# FPGA_Peripherals_Control.net
KiCad netlist of a schematic drawn in Altium Designer
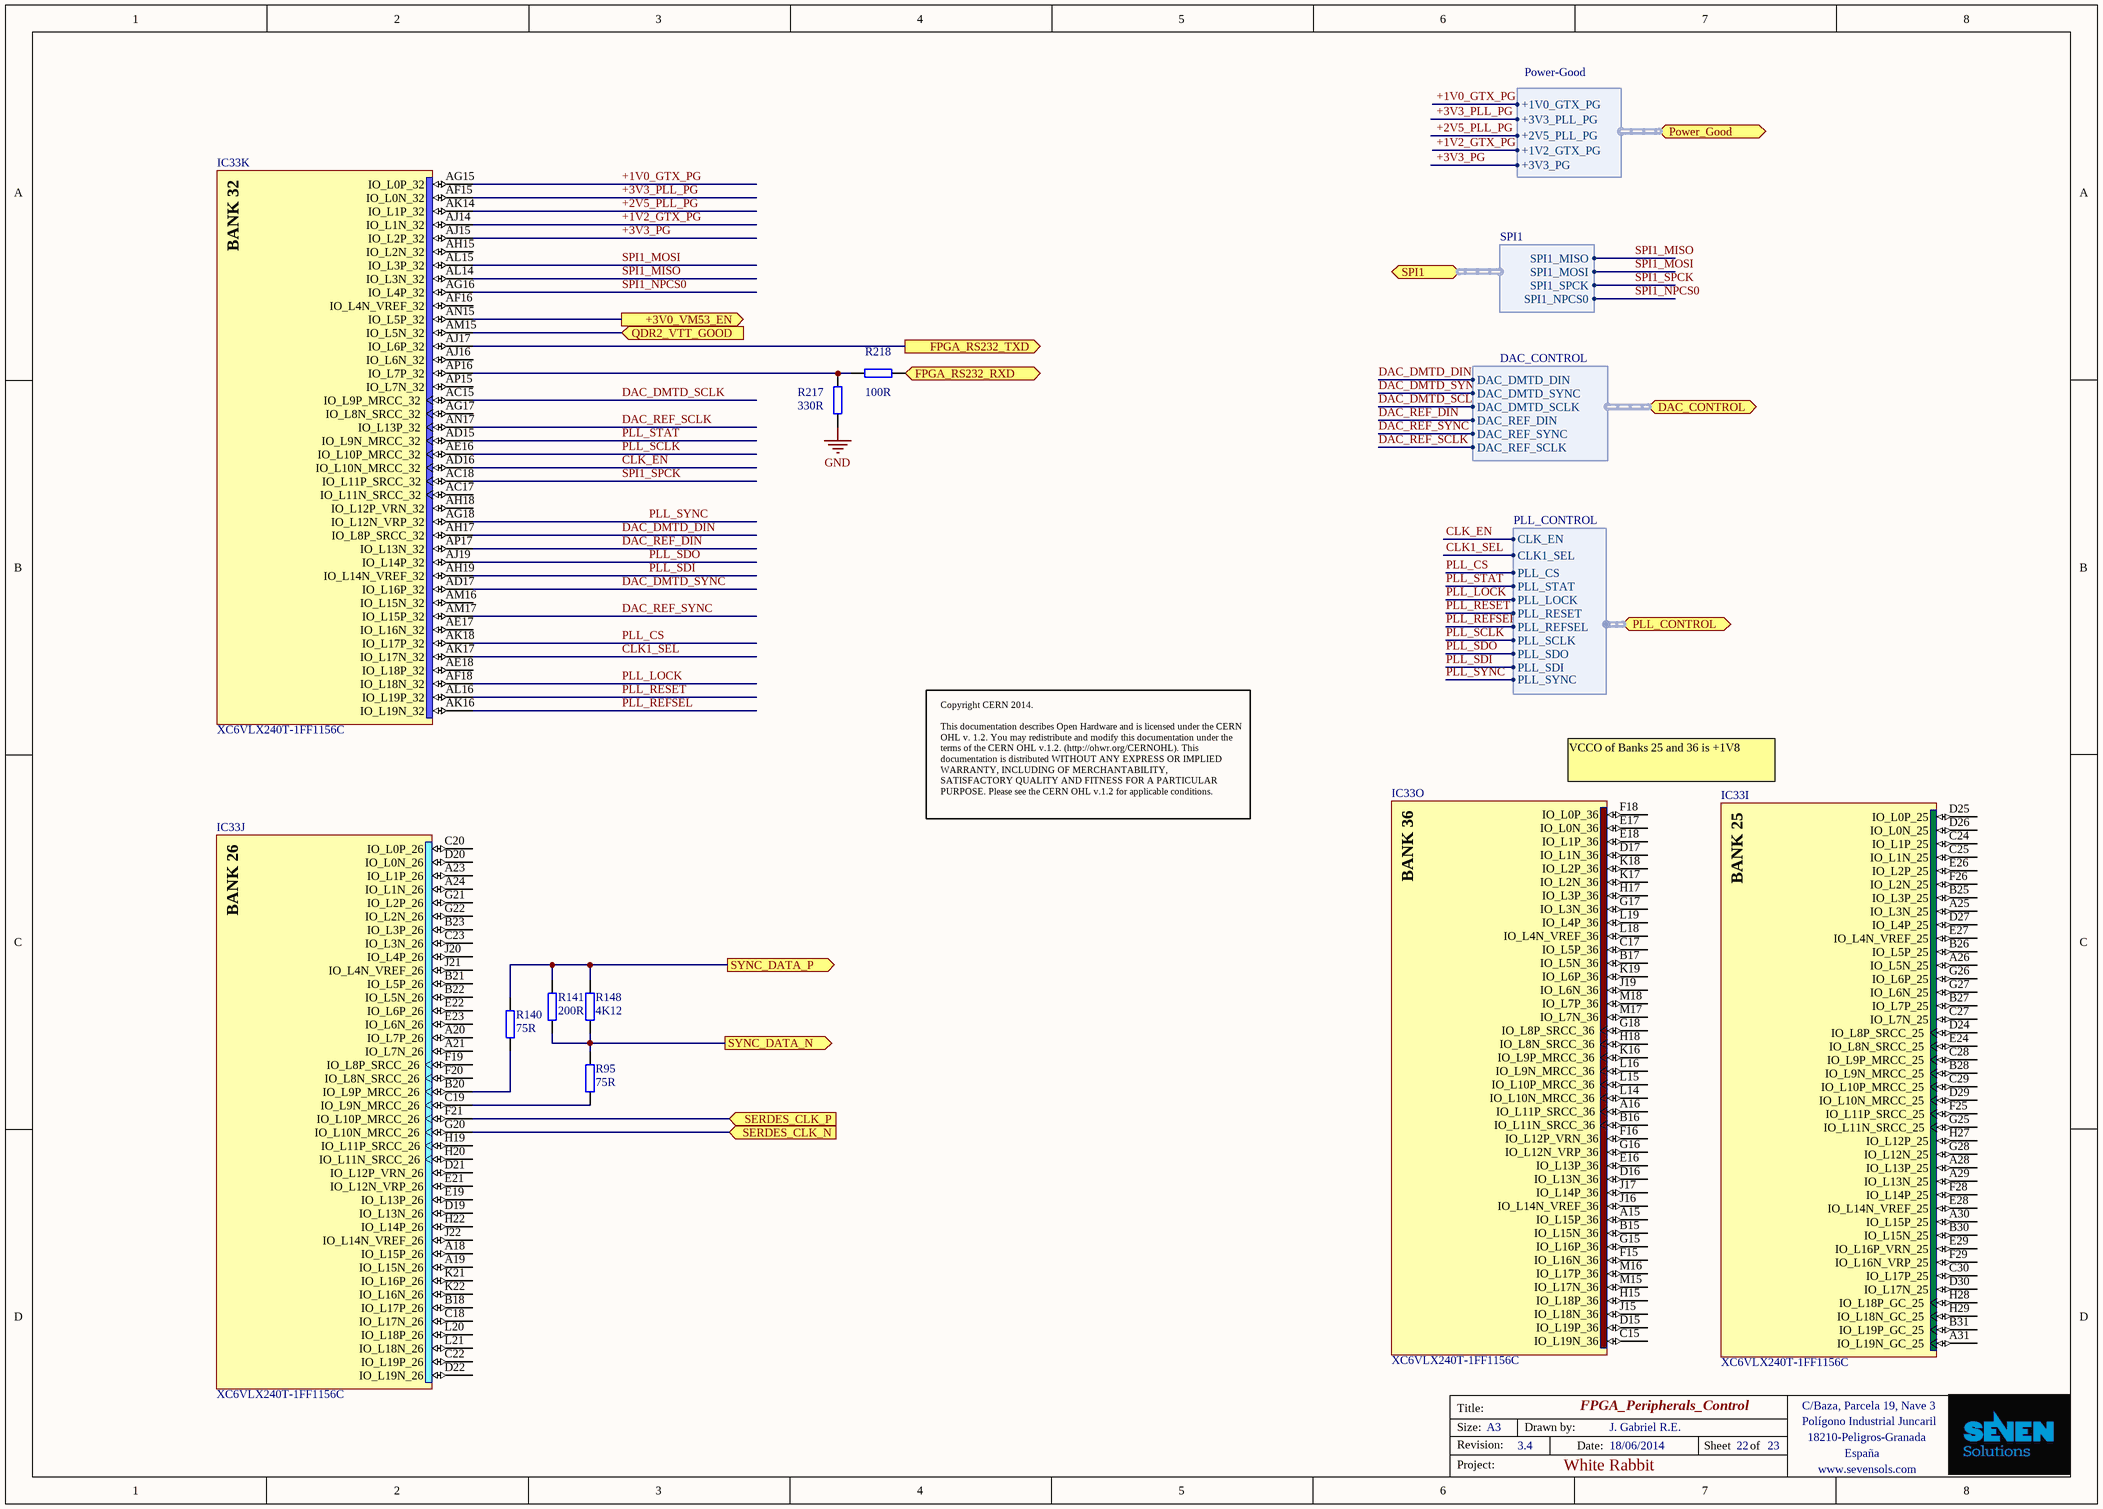
[diagram p0: FPGA_Peripherals_Control.SchDoc]

(export (version "E")
  (design (tool "Eeschema 10.0.6"))
  (components
    (comp (ref "IC33")
      (value "XC6VLX240T-1FF1156C")
      (footprint "FF1156")
      (fields (field (name "PUBLISHER") "Altium Limited"))
      (libsource (lib "Xilinx Virtex-6") (part "XC6VLX240T-1FF1156C"))
    )
    (comp (ref "R95")
      (value "75R")
      (footprint "0402")
      (description "SMD Resistor")
      (fields (field (name "TOLERANCE") "±1%"))
      (libsource (lib "wr_switch") (part "RES_SMD"))
    )
    (comp (ref "R140")
      (value "75R")
      (footprint "0402")
      (description "SMD Resistor")
      (fields (field (name "TOLERANCE") "±1%"))
      (libsource (lib "wr_switch") (part "RES_SMD"))
    )
    (comp (ref "R141")
      (value "200R")
      (footprint "0402")
      (description "SMD Resistor")
      (fields (field (name "TOLERANCE") "±1%"))
      (libsource (lib "wr_switch") (part "RES_SMD"))
    )
    (comp (ref "R148")
      (value "4K12")
      (footprint "0402")
      (description "SMD Resistor")
      (fields (field (name "TOLERANCE") "±1%"))
      (libsource (lib "wr_switch") (part "RES_SMD"))
    )
    (comp (ref "R217")
      (value "330R")
      (footprint "0402")
      (description "SMD Resistor")
      (fields (field (name "TOLERANCE") "±1%"))
      (libsource (lib "wr_switch") (part "RES_SMD"))
    )
    (comp (ref "R218")
      (value "100R")
      (footprint "0402")
      (description "SMD Resistor")
      (fields (field (name "TOLERANCE") "±1%"))
      (libsource (lib "wr_switch") (part "RES_SMD"))
    )
  )
  (nets
    (net (code "5") (name "/+1V0_GTX_PG") (class "Default")
      (node (ref "IC33") (pin "AG15") (pinfunction "IO_L0P_32_AG15") (pintype "bidirectional"))
    )
    (net (code "6") (name "/+1V2_GTX_PG") (class "Default")
      (node (ref "IC33") (pin "AJ14") (pinfunction "IO_L1N_32_AJ14") (pintype "bidirectional"))
    )
    (net (code "7") (name "/+2V5_PLL_PG") (class "Default")
      (node (ref "IC33") (pin "AK14") (pinfunction "IO_L1P_32_AK14") (pintype "bidirectional"))
    )
    (net (code "8") (name "/+3V0_VM53_EN") (class "Default")
      (node (ref "IC33") (pin "AN15") (pinfunction "IO_L5P_32_AN15") (pintype "bidirectional"))
    )
    (net (code "9") (name "/+3V3_PG") (class "Default")
      (node (ref "IC33") (pin "AJ15") (pinfunction "IO_L2P_32_AJ15") (pintype "bidirectional"))
    )
    (net (code "10") (name "/+3V3_PLL_PG") (class "Default")
      (node (ref "IC33") (pin "AF15") (pinfunction "IO_L0N_32_AF15") (pintype "bidirectional"))
    )
    (net (code "11") (name "/CLK1_SEL") (class "Default")
      (node (ref "IC33") (pin "AK17") (pinfunction "IO_L17N_32_AK17") (pintype "bidirectional"))
    )
    (net (code "12") (name "/CLK_EN") (class "Default")
      (node (ref "IC33") (pin "AD16") (pinfunction "IO_L10N_MRCC_32_AD16") (pintype "bidirectional"))
    )
    (net (code "13") (name "/DAC_DMTD_DIN") (class "Default")
      (node (ref "IC33") (pin "AH17") (pinfunction "IO_L8P_SRCC_32_AH17") (pintype "bidirectional"))
    )
    (net (code "14") (name "/DAC_DMTD_SCLK") (class "Default")
      (node (ref "IC33") (pin "AC15") (pinfunction "IO_L9P_MRCC_32_AC15") (pintype "bidirectional"))
    )
    (net (code "15") (name "/DAC_DMTD_SYNC") (class "Default")
      (node (ref "IC33") (pin "AD17") (pinfunction "IO_L16P_32_AD17") (pintype "bidirectional"))
    )
    (net (code "16") (name "/DAC_REF_DIN") (class "Default")
      (node (ref "IC33") (pin "AP17") (pinfunction "IO_L13N_32_AP17") (pintype "bidirectional"))
    )
    (net (code "17") (name "/DAC_REF_SCLK") (class "Default")
      (node (ref "IC33") (pin "AN17") (pinfunction "IO_L13P_32_AN17") (pintype "bidirectional"))
    )
    (net (code "18") (name "/DAC_REF_SYNC") (class "Default")
      (node (ref "IC33") (pin "AM17") (pinfunction "IO_L15P_32_AM17") (pintype "bidirectional"))
    )
    (net (code "19") (name "/FPGA_RS232_RXD") (class "Default")
      (node (ref "R218") (pin "1") (pinfunction "1_1") (pintype "passive"))
    )
    (net (code "20") (name "/FPGA_RS232_TXD") (class "Default")
      (node (ref "IC33") (pin "AJ17") (pinfunction "IO_L6P_32_AJ17") (pintype "bidirectional"))
    )
    (net (code "21") (name "/PLL_CS") (class "Default")
      (node (ref "IC33") (pin "AK18") (pinfunction "IO_L17P_32_AK18") (pintype "bidirectional"))
    )
    (net (code "22") (name "/PLL_LOCK") (class "Default")
      (node (ref "IC33") (pin "AF18") (pinfunction "IO_L18N_32_AF18") (pintype "bidirectional"))
    )
    (net (code "23") (name "/PLL_REFSEL") (class "Default")
      (node (ref "IC33") (pin "AK16") (pinfunction "IO_L19N_32_AK16") (pintype "bidirectional"))
    )
    (net (code "24") (name "/PLL_RESET") (class "Default")
      (node (ref "IC33") (pin "AL16") (pinfunction "IO_L19P_32_AL16") (pintype "bidirectional"))
    )
    (net (code "25") (name "/PLL_SCLK") (class "Default")
      (node (ref "IC33") (pin "AE16") (pinfunction "IO_L10P_MRCC_32_AE16") (pintype "bidirectional"))
    )
    (net (code "26") (name "/PLL_SDI") (class "Default")
      (node (ref "IC33") (pin "AH19") (pinfunction "IO_L14N_VREF_32_AH19") (pintype "bidirectional"))
    )
    (net (code "27") (name "/PLL_SDO") (class "Default")
      (node (ref "IC33") (pin "AJ19") (pinfunction "IO_L14P_32_AJ19") (pintype "bidirectional"))
    )
    (net (code "28") (name "/PLL_STAT") (class "Default")
      (node (ref "IC33") (pin "AD15") (pinfunction "IO_L9N_MRCC_32_AD15") (pintype "bidirectional"))
    )
    (net (code "29") (name "/PLL_SYNC") (class "Default")
      (node (ref "IC33") (pin "AG18") (pinfunction "IO_L12N_VRP_32_AG18") (pintype "bidirectional"))
    )
    (net (code "30") (name "/QDR2_VTT_GOOD") (class "Default")
      (node (ref "IC33") (pin "AM15") (pinfunction "IO_L5N_32_AM15") (pintype "bidirectional"))
    )
    (net (code "31") (name "/SERDES_CLK_N") (class "Default")
      (node (ref "IC33") (pin "G20") (pinfunction "IO_L10N_MRCC_26_G20") (pintype "bidirectional"))
    )
    (net (code "32") (name "/SERDES_CLK_P") (class "Default")
      (node (ref "IC33") (pin "F21") (pinfunction "IO_L10P_MRCC_26_F21") (pintype "bidirectional"))
    )
    (net (code "33") (name "/SPI1_MISO") (class "Default")
      (node (ref "IC33") (pin "AL14") (pinfunction "IO_L3N_32_AL14") (pintype "bidirectional"))
    )
    (net (code "34") (name "/SPI1_MOSI") (class "Default")
      (node (ref "IC33") (pin "AL15") (pinfunction "IO_L3P_32_AL15") (pintype "bidirectional"))
    )
    (net (code "35") (name "/SPI1_NPCS0") (class "Default")
      (node (ref "IC33") (pin "AG16") (pinfunction "IO_L4P_32_AG16") (pintype "bidirectional"))
    )
    (net (code "36") (name "/SPI1_SPCK") (class "Default")
      (node (ref "IC33") (pin "AC18") (pinfunction "IO_L11P_SRCC_32_AC18") (pintype "bidirectional"))
    )
    (net (code "37") (name "/SYNC_DATA_N") (class "Default")
      (node (ref "R141") (pin "2") (pinfunction "2_2") (pintype "passive"))
      (node (ref "R148") (pin "1") (pinfunction "1_1") (pintype "passive"))
      (node (ref "R95") (pin "2") (pinfunction "2_2") (pintype "passive"))
    )
    (net (code "38") (name "/SYNC_DATA_P") (class "Default")
      (node (ref "R140") (pin "2") (pinfunction "2_2") (pintype "passive"))
      (node (ref "R141") (pin "1") (pinfunction "1_1") (pintype "passive"))
      (node (ref "R148") (pin "2") (pinfunction "2_2") (pintype "passive"))
    )
    (net (code "43") (name "GND") (class "Default")
      (node (ref "R217") (pin "1") (pinfunction "1_1") (pintype "passive"))
    )
    (net (code "44") (name "Net-(IC33J-IO_L9N_MRCC_26)") (class "Default")
      (node (ref "IC33") (pin "C19") (pinfunction "IO_L9N_MRCC_26_C19") (pintype "bidirectional"))
      (node (ref "R95") (pin "1") (pinfunction "1_1") (pintype "passive"))
    )
    (net (code "45") (name "Net-(IC33J-IO_L9P_MRCC_26)") (class "Default")
      (node (ref "IC33") (pin "B20") (pinfunction "IO_L9P_MRCC_26_B20") (pintype "bidirectional"))
      (node (ref "R140") (pin "1") (pinfunction "1_1") (pintype "passive"))
    )
    (net (code "46") (name "Net-(IC33K-IO_L7P_32)") (class "Default")
      (node (ref "IC33") (pin "AP16") (pinfunction "IO_L7P_32_AP16") (pintype "bidirectional"))
      (node (ref "R217") (pin "2") (pinfunction "2_2") (pintype "passive"))
      (node (ref "R218") (pin "2") (pinfunction "2_2") (pintype "passive"))
    )
    (net (code "47") (name "unconnected-(IC33I-IO_L0N_25-PadD26)") (class "Default")
      (node (ref "IC33") (pin "D26") (pinfunction "IO_L0N_25_D26") (pintype "bidirectional"))
    )
    (net (code "48") (name "unconnected-(IC33I-IO_L0P_25-PadD25)") (class "Default")
      (node (ref "IC33") (pin "D25") (pinfunction "IO_L0P_25_D25") (pintype "bidirectional"))
    )
    (net (code "49") (name "unconnected-(IC33I-IO_L1N_25-PadC25)") (class "Default")
      (node (ref "IC33") (pin "C25") (pinfunction "IO_L1N_25_C25") (pintype "bidirectional"))
    )
    (net (code "50") (name "unconnected-(IC33I-IO_L1P_25-PadC24)") (class "Default")
      (node (ref "IC33") (pin "C24") (pinfunction "IO_L1P_25_C24") (pintype "bidirectional"))
    )
    (net (code "51") (name "unconnected-(IC33I-IO_L2N_25-PadF26)") (class "Default")
      (node (ref "IC33") (pin "F26") (pinfunction "IO_L2N_25_F26") (pintype "bidirectional"))
    )
    (net (code "52") (name "unconnected-(IC33I-IO_L2P_25-PadE26)") (class "Default")
      (node (ref "IC33") (pin "E26") (pinfunction "IO_L2P_25_E26") (pintype "bidirectional"))
    )
    (net (code "53") (name "unconnected-(IC33I-IO_L3N_25-PadA25)") (class "Default")
      (node (ref "IC33") (pin "A25") (pinfunction "IO_L3N_25_A25") (pintype "bidirectional"))
    )
    (net (code "54") (name "unconnected-(IC33I-IO_L3P_25-PadB25)") (class "Default")
      (node (ref "IC33") (pin "B25") (pinfunction "IO_L3P_25_B25") (pintype "bidirectional"))
    )
    (net (code "55") (name "unconnected-(IC33I-IO_L4N_VREF_25-PadE27)") (class "Default")
      (node (ref "IC33") (pin "E27") (pinfunction "IO_L4N_VREF_25_E27") (pintype "bidirectional"))
    )
    (net (code "56") (name "unconnected-(IC33I-IO_L4P_25-PadD27)") (class "Default")
      (node (ref "IC33") (pin "D27") (pinfunction "IO_L4P_25_D27") (pintype "bidirectional"))
    )
    (net (code "57") (name "unconnected-(IC33I-IO_L5N_25-PadA26)") (class "Default")
      (node (ref "IC33") (pin "A26") (pinfunction "IO_L5N_25_A26") (pintype "bidirectional"))
    )
    (net (code "58") (name "unconnected-(IC33I-IO_L5P_25-PadB26)") (class "Default")
      (node (ref "IC33") (pin "B26") (pinfunction "IO_L5P_25_B26") (pintype "bidirectional"))
    )
    (net (code "59") (name "unconnected-(IC33I-IO_L6N_25-PadG27)") (class "Default")
      (node (ref "IC33") (pin "G27") (pinfunction "IO_L6N_25_G27") (pintype "bidirectional"))
    )
    (net (code "60") (name "unconnected-(IC33I-IO_L6P_25-PadG26)") (class "Default")
      (node (ref "IC33") (pin "G26") (pinfunction "IO_L6P_25_G26") (pintype "bidirectional"))
    )
    (net (code "61") (name "unconnected-(IC33I-IO_L7N_25-PadC27)") (class "Default")
      (node (ref "IC33") (pin "C27") (pinfunction "IO_L7N_25_C27") (pintype "bidirectional"))
    )
    (net (code "62") (name "unconnected-(IC33I-IO_L7P_25-PadB27)") (class "Default")
      (node (ref "IC33") (pin "B27") (pinfunction "IO_L7P_25_B27") (pintype "bidirectional"))
    )
    (net (code "63") (name "unconnected-(IC33I-IO_L8N_SRCC_25-PadE24)") (class "Default")
      (node (ref "IC33") (pin "E24") (pinfunction "IO_L8N_SRCC_25_E24") (pintype "bidirectional"))
    )
    (net (code "64") (name "unconnected-(IC33I-IO_L8P_SRCC_25-PadD24)") (class "Default")
      (node (ref "IC33") (pin "D24") (pinfunction "IO_L8P_SRCC_25_D24") (pintype "bidirectional"))
    )
    (net (code "65") (name "unconnected-(IC33I-IO_L9N_MRCC_25-PadB28)") (class "Default")
      (node (ref "IC33") (pin "B28") (pinfunction "IO_L9N_MRCC_25_B28") (pintype "bidirectional"))
    )
    (net (code "66") (name "unconnected-(IC33I-IO_L9P_MRCC_25-PadC28)") (class "Default")
      (node (ref "IC33") (pin "C28") (pinfunction "IO_L9P_MRCC_25_C28") (pintype "bidirectional"))
    )
    (net (code "67") (name "unconnected-(IC33I-IO_L10N_MRCC_25-PadD29)") (class "Default")
      (node (ref "IC33") (pin "D29") (pinfunction "IO_L10N_MRCC_25_D29") (pintype "bidirectional"))
    )
    (net (code "68") (name "unconnected-(IC33I-IO_L10P_MRCC_25-PadC29)") (class "Default")
      (node (ref "IC33") (pin "C29") (pinfunction "IO_L10P_MRCC_25_C29") (pintype "bidirectional"))
    )
    (net (code "69") (name "unconnected-(IC33I-IO_L11N_SRCC_25-PadG25)") (class "Default")
      (node (ref "IC33") (pin "G25") (pinfunction "IO_L11N_SRCC_25_G25") (pintype "bidirectional"))
    )
    (net (code "70") (name "unconnected-(IC33I-IO_L11P_SRCC_25-PadF25)") (class "Default")
      (node (ref "IC33") (pin "F25") (pinfunction "IO_L11P_SRCC_25_F25") (pintype "bidirectional"))
    )
    (net (code "71") (name "unconnected-(IC33I-IO_L12N_25-PadG28)") (class "Default")
      (node (ref "IC33") (pin "G28") (pinfunction "IO_L12N_25_G28") (pintype "bidirectional"))
    )
    (net (code "72") (name "unconnected-(IC33I-IO_L12P_25-PadH27)") (class "Default")
      (node (ref "IC33") (pin "H27") (pinfunction "IO_L12P_25_H27") (pintype "bidirectional"))
    )
    (net (code "73") (name "unconnected-(IC33I-IO_L13N_25-PadA29)") (class "Default")
      (node (ref "IC33") (pin "A29") (pinfunction "IO_L13N_25_A29") (pintype "bidirectional"))
    )
    (net (code "74") (name "unconnected-(IC33I-IO_L13P_25-PadA28)") (class "Default")
      (node (ref "IC33") (pin "A28") (pinfunction "IO_L13P_25_A28") (pintype "bidirectional"))
    )
    (net (code "75") (name "unconnected-(IC33I-IO_L14N_VREF_25-PadE28)") (class "Default")
      (node (ref "IC33") (pin "E28") (pinfunction "IO_L14N_VREF_25_E28") (pintype "bidirectional"))
    )
    (net (code "76") (name "unconnected-(IC33I-IO_L14P_25-PadF28)") (class "Default")
      (node (ref "IC33") (pin "F28") (pinfunction "IO_L14P_25_F28") (pintype "bidirectional"))
    )
    (net (code "77") (name "unconnected-(IC33I-IO_L15N_25-PadB30)") (class "Default")
      (node (ref "IC33") (pin "B30") (pinfunction "IO_L15N_25_B30") (pintype "bidirectional"))
    )
    (net (code "78") (name "unconnected-(IC33I-IO_L15P_25-PadA30)") (class "Default")
      (node (ref "IC33") (pin "A30") (pinfunction "IO_L15P_25_A30") (pintype "bidirectional"))
    )
    (net (code "79") (name "unconnected-(IC33I-IO_L16N_VRP_25-PadF29)") (class "Default")
      (node (ref "IC33") (pin "F29") (pinfunction "IO_L16N_VRP_25_F29") (pintype "bidirectional"))
    )
    (net (code "80") (name "unconnected-(IC33I-IO_L16P_VRN_25-PadE29)") (class "Default")
      (node (ref "IC33") (pin "E29") (pinfunction "IO_L16P_VRN_25_E29") (pintype "bidirectional"))
    )
    (net (code "81") (name "unconnected-(IC33I-IO_L17N_25-PadD30)") (class "Default")
      (node (ref "IC33") (pin "D30") (pinfunction "IO_L17N_25_D30") (pintype "bidirectional"))
    )
    (net (code "82") (name "unconnected-(IC33I-IO_L17P_25-PadC30)") (class "Default")
      (node (ref "IC33") (pin "C30") (pinfunction "IO_L17P_25_C30") (pintype "bidirectional"))
    )
    (net (code "83") (name "unconnected-(IC33I-IO_L18N_GC_25-PadH29)") (class "Default")
      (node (ref "IC33") (pin "H29") (pinfunction "IO_L18N_GC_25_H29") (pintype "bidirectional"))
    )
    (net (code "84") (name "unconnected-(IC33I-IO_L18P_GC_25-PadH28)") (class "Default")
      (node (ref "IC33") (pin "H28") (pinfunction "IO_L18P_GC_25_H28") (pintype "bidirectional"))
    )
    (net (code "85") (name "unconnected-(IC33I-IO_L19N_GC_25-PadA31)") (class "Default")
      (node (ref "IC33") (pin "A31") (pinfunction "IO_L19N_GC_25_A31") (pintype "bidirectional"))
    )
    (net (code "86") (name "unconnected-(IC33I-IO_L19P_GC_25-PadB31)") (class "Default")
      (node (ref "IC33") (pin "B31") (pinfunction "IO_L19P_GC_25_B31") (pintype "bidirectional"))
    )
    (net (code "87") (name "unconnected-(IC33J-IO_L0N_26-PadD20)") (class "Default")
      (node (ref "IC33") (pin "D20") (pinfunction "IO_L0N_26_D20") (pintype "bidirectional"))
    )
    (net (code "88") (name "unconnected-(IC33J-IO_L0P_26-PadC20)") (class "Default")
      (node (ref "IC33") (pin "C20") (pinfunction "IO_L0P_26_C20") (pintype "bidirectional"))
    )
    (net (code "89") (name "unconnected-(IC33J-IO_L1N_26-PadA24)") (class "Default")
      (node (ref "IC33") (pin "A24") (pinfunction "IO_L1N_26_A24") (pintype "bidirectional"))
    )
    (net (code "90") (name "unconnected-(IC33J-IO_L1P_26-PadA23)") (class "Default")
      (node (ref "IC33") (pin "A23") (pinfunction "IO_L1P_26_A23") (pintype "bidirectional"))
    )
    (net (code "91") (name "unconnected-(IC33J-IO_L2N_26-PadG22)") (class "Default")
      (node (ref "IC33") (pin "G22") (pinfunction "IO_L2N_26_G22") (pintype "bidirectional"))
    )
    (net (code "92") (name "unconnected-(IC33J-IO_L2P_26-PadG21)") (class "Default")
      (node (ref "IC33") (pin "G21") (pinfunction "IO_L2P_26_G21") (pintype "bidirectional"))
    )
    (net (code "93") (name "unconnected-(IC33J-IO_L3N_26-PadC23)") (class "Default")
      (node (ref "IC33") (pin "C23") (pinfunction "IO_L3N_26_C23") (pintype "bidirectional"))
    )
    (net (code "94") (name "unconnected-(IC33J-IO_L3P_26-PadB23)") (class "Default")
      (node (ref "IC33") (pin "B23") (pinfunction "IO_L3P_26_B23") (pintype "bidirectional"))
    )
    (net (code "95") (name "unconnected-(IC33J-IO_L4N_VREF_26-PadJ21)") (class "Default")
      (node (ref "IC33") (pin "J21") (pinfunction "IO_L4N_VREF_26_J21") (pintype "bidirectional"))
    )
    (net (code "96") (name "unconnected-(IC33J-IO_L4P_26-PadJ20)") (class "Default")
      (node (ref "IC33") (pin "J20") (pinfunction "IO_L4P_26_J20") (pintype "bidirectional"))
    )
    (net (code "97") (name "unconnected-(IC33J-IO_L5N_26-PadB22)") (class "Default")
      (node (ref "IC33") (pin "B22") (pinfunction "IO_L5N_26_B22") (pintype "bidirectional"))
    )
    (net (code "98") (name "unconnected-(IC33J-IO_L5P_26-PadB21)") (class "Default")
      (node (ref "IC33") (pin "B21") (pinfunction "IO_L5P_26_B21") (pintype "bidirectional"))
    )
    (net (code "99") (name "unconnected-(IC33J-IO_L6N_26-PadE23)") (class "Default")
      (node (ref "IC33") (pin "E23") (pinfunction "IO_L6N_26_E23") (pintype "bidirectional"))
    )
    (net (code "100") (name "unconnected-(IC33J-IO_L6P_26-PadE22)") (class "Default")
      (node (ref "IC33") (pin "E22") (pinfunction "IO_L6P_26_E22") (pintype "bidirectional"))
    )
    (net (code "101") (name "unconnected-(IC33J-IO_L7N_26-PadA21)") (class "Default")
      (node (ref "IC33") (pin "A21") (pinfunction "IO_L7N_26_A21") (pintype "bidirectional"))
    )
    (net (code "102") (name "unconnected-(IC33J-IO_L7P_26-PadA20)") (class "Default")
      (node (ref "IC33") (pin "A20") (pinfunction "IO_L7P_26_A20") (pintype "bidirectional"))
    )
    (net (code "103") (name "unconnected-(IC33J-IO_L8N_SRCC_26-PadF20)") (class "Default")
      (node (ref "IC33") (pin "F20") (pinfunction "IO_L8N_SRCC_26_F20") (pintype "bidirectional"))
    )
    (net (code "104") (name "unconnected-(IC33J-IO_L8P_SRCC_26-PadF19)") (class "Default")
      (node (ref "IC33") (pin "F19") (pinfunction "IO_L8P_SRCC_26_F19") (pintype "bidirectional"))
    )
    (net (code "105") (name "unconnected-(IC33J-IO_L11N_SRCC_26-PadH20)") (class "Default")
      (node (ref "IC33") (pin "H20") (pinfunction "IO_L11N_SRCC_26_H20") (pintype "bidirectional"))
    )
    (net (code "106") (name "unconnected-(IC33J-IO_L11P_SRCC_26-PadH19)") (class "Default")
      (node (ref "IC33") (pin "H19") (pinfunction "IO_L11P_SRCC_26_H19") (pintype "bidirectional"))
    )
    (net (code "107") (name "unconnected-(IC33J-IO_L12N_VRP_26-PadE21)") (class "Default")
      (node (ref "IC33") (pin "E21") (pinfunction "IO_L12N_VRP_26_E21") (pintype "bidirectional"))
    )
    (net (code "108") (name "unconnected-(IC33J-IO_L12P_VRN_26-PadD21)") (class "Default")
      (node (ref "IC33") (pin "D21") (pinfunction "IO_L12P_VRN_26_D21") (pintype "bidirectional"))
    )
    (net (code "109") (name "unconnected-(IC33J-IO_L13N_26-PadD19)") (class "Default")
      (node (ref "IC33") (pin "D19") (pinfunction "IO_L13N_26_D19") (pintype "bidirectional"))
    )
    (net (code "110") (name "unconnected-(IC33J-IO_L13P_26-PadE19)") (class "Default")
      (node (ref "IC33") (pin "E19") (pinfunction "IO_L13P_26_E19") (pintype "bidirectional"))
    )
    (net (code "111") (name "unconnected-(IC33J-IO_L14N_VREF_26-PadJ22)") (class "Default")
      (node (ref "IC33") (pin "J22") (pinfunction "IO_L14N_VREF_26_J22") (pintype "bidirectional"))
    )
    (net (code "112") (name "unconnected-(IC33J-IO_L14P_26-PadH22)") (class "Default")
      (node (ref "IC33") (pin "H22") (pinfunction "IO_L14P_26_H22") (pintype "bidirectional"))
    )
    (net (code "113") (name "unconnected-(IC33J-IO_L15N_26-PadA19)") (class "Default")
      (node (ref "IC33") (pin "A19") (pinfunction "IO_L15N_26_A19") (pintype "bidirectional"))
    )
    (net (code "114") (name "unconnected-(IC33J-IO_L15P_26-PadA18)") (class "Default")
      (node (ref "IC33") (pin "A18") (pinfunction "IO_L15P_26_A18") (pintype "bidirectional"))
    )
    (net (code "115") (name "unconnected-(IC33J-IO_L16N_26-PadK22)") (class "Default")
      (node (ref "IC33") (pin "K22") (pinfunction "IO_L16N_26_K22") (pintype "bidirectional"))
    )
    (net (code "116") (name "unconnected-(IC33J-IO_L16P_26-PadK21)") (class "Default")
      (node (ref "IC33") (pin "K21") (pinfunction "IO_L16P_26_K21") (pintype "bidirectional"))
    )
    (net (code "117") (name "unconnected-(IC33J-IO_L17N_26-PadC18)") (class "Default")
      (node (ref "IC33") (pin "C18") (pinfunction "IO_L17N_26_C18") (pintype "bidirectional"))
    )
    (net (code "118") (name "unconnected-(IC33J-IO_L17P_26-PadB18)") (class "Default")
      (node (ref "IC33") (pin "B18") (pinfunction "IO_L17P_26_B18") (pintype "bidirectional"))
    )
    (net (code "119") (name "unconnected-(IC33J-IO_L18N_26-PadL21)") (class "Default")
      (node (ref "IC33") (pin "L21") (pinfunction "IO_L18N_26_L21") (pintype "bidirectional"))
    )
    (net (code "120") (name "unconnected-(IC33J-IO_L18P_26-PadL20)") (class "Default")
      (node (ref "IC33") (pin "L20") (pinfunction "IO_L18P_26_L20") (pintype "bidirectional"))
    )
    (net (code "121") (name "unconnected-(IC33J-IO_L19N_26-PadD22)") (class "Default")
      (node (ref "IC33") (pin "D22") (pinfunction "IO_L19N_26_D22") (pintype "bidirectional"))
    )
    (net (code "122") (name "unconnected-(IC33J-IO_L19P_26-PadC22)") (class "Default")
      (node (ref "IC33") (pin "C22") (pinfunction "IO_L19P_26_C22") (pintype "bidirectional"))
    )
    (net (code "123") (name "unconnected-(IC33K-IO_L2N_32-PadAH15)") (class "Default")
      (node (ref "IC33") (pin "AH15") (pinfunction "IO_L2N_32_AH15") (pintype "bidirectional"))
    )
    (net (code "124") (name "unconnected-(IC33K-IO_L4N_VREF_32-PadAF16)") (class "Default")
      (node (ref "IC33") (pin "AF16") (pinfunction "IO_L4N_VREF_32_AF16") (pintype "bidirectional"))
    )
    (net (code "125") (name "unconnected-(IC33K-IO_L6N_32-PadAJ16)") (class "Default")
      (node (ref "IC33") (pin "AJ16") (pinfunction "IO_L6N_32_AJ16") (pintype "bidirectional"))
    )
    (net (code "126") (name "unconnected-(IC33K-IO_L7N_32-PadAP15)") (class "Default")
      (node (ref "IC33") (pin "AP15") (pinfunction "IO_L7N_32_AP15") (pintype "bidirectional"))
    )
    (net (code "127") (name "unconnected-(IC33K-IO_L8N_SRCC_32-PadAG17)") (class "Default")
      (node (ref "IC33") (pin "AG17") (pinfunction "IO_L8N_SRCC_32_AG17") (pintype "bidirectional"))
    )
    (net (code "128") (name "unconnected-(IC33K-IO_L11N_SRCC_32-PadAC17)") (class "Default")
      (node (ref "IC33") (pin "AC17") (pinfunction "IO_L11N_SRCC_32_AC17") (pintype "bidirectional"))
    )
    (net (code "129") (name "unconnected-(IC33K-IO_L12P_VRN_32-PadAH18)") (class "Default")
      (node (ref "IC33") (pin "AH18") (pinfunction "IO_L12P_VRN_32_AH18") (pintype "bidirectional"))
    )
    (net (code "130") (name "unconnected-(IC33K-IO_L15N_32-PadAM16)") (class "Default")
      (node (ref "IC33") (pin "AM16") (pinfunction "IO_L15N_32_AM16") (pintype "bidirectional"))
    )
    (net (code "131") (name "unconnected-(IC33K-IO_L16N_32-PadAE17)") (class "Default")
      (node (ref "IC33") (pin "AE17") (pinfunction "IO_L16N_32_AE17") (pintype "bidirectional"))
    )
    (net (code "132") (name "unconnected-(IC33K-IO_L18P_32-PadAE18)") (class "Default")
      (node (ref "IC33") (pin "AE18") (pinfunction "IO_L18P_32_AE18") (pintype "bidirectional"))
    )
    (net (code "133") (name "unconnected-(IC33O-IO_L0N_36-PadE17)") (class "Default")
      (node (ref "IC33") (pin "E17") (pinfunction "IO_L0N_36_E17") (pintype "bidirectional"))
    )
    (net (code "134") (name "unconnected-(IC33O-IO_L0P_36-PadF18)") (class "Default")
      (node (ref "IC33") (pin "F18") (pinfunction "IO_L0P_36_F18") (pintype "bidirectional"))
    )
    (net (code "135") (name "unconnected-(IC33O-IO_L1N_36-PadD17)") (class "Default")
      (node (ref "IC33") (pin "D17") (pinfunction "IO_L1N_36_D17") (pintype "bidirectional"))
    )
    (net (code "136") (name "unconnected-(IC33O-IO_L1P_36-PadE18)") (class "Default")
      (node (ref "IC33") (pin "E18") (pinfunction "IO_L1P_36_E18") (pintype "bidirectional"))
    )
    (net (code "137") (name "unconnected-(IC33O-IO_L2N_36-PadK17)") (class "Default")
      (node (ref "IC33") (pin "K17") (pinfunction "IO_L2N_36_K17") (pintype "bidirectional"))
    )
    (net (code "138") (name "unconnected-(IC33O-IO_L2P_36-PadK18)") (class "Default")
      (node (ref "IC33") (pin "K18") (pinfunction "IO_L2P_36_K18") (pintype "bidirectional"))
    )
    (net (code "139") (name "unconnected-(IC33O-IO_L3N_36-PadG17)") (class "Default")
      (node (ref "IC33") (pin "G17") (pinfunction "IO_L3N_36_G17") (pintype "bidirectional"))
    )
    (net (code "140") (name "unconnected-(IC33O-IO_L3P_36-PadH17)") (class "Default")
      (node (ref "IC33") (pin "H17") (pinfunction "IO_L3P_36_H17") (pintype "bidirectional"))
    )
    (net (code "141") (name "unconnected-(IC33O-IO_L4N_VREF_36-PadL18)") (class "Default")
      (node (ref "IC33") (pin "L18") (pinfunction "IO_L4N_VREF_36_L18") (pintype "bidirectional"))
    )
    (net (code "142") (name "unconnected-(IC33O-IO_L4P_36-PadL19)") (class "Default")
      (node (ref "IC33") (pin "L19") (pinfunction "IO_L4P_36_L19") (pintype "bidirectional"))
    )
    (net (code "143") (name "unconnected-(IC33O-IO_L5N_36-PadB17)") (class "Default")
      (node (ref "IC33") (pin "B17") (pinfunction "IO_L5N_36_B17") (pintype "bidirectional"))
    )
    (net (code "144") (name "unconnected-(IC33O-IO_L5P_36-PadC17)") (class "Default")
      (node (ref "IC33") (pin "C17") (pinfunction "IO_L5P_36_C17") (pintype "bidirectional"))
    )
    (net (code "145") (name "unconnected-(IC33O-IO_L6N_36-PadJ19)") (class "Default")
      (node (ref "IC33") (pin "J19") (pinfunction "IO_L6N_36_J19") (pintype "bidirectional"))
    )
    (net (code "146") (name "unconnected-(IC33O-IO_L6P_36-PadK19)") (class "Default")
      (node (ref "IC33") (pin "K19") (pinfunction "IO_L6P_36_K19") (pintype "bidirectional"))
    )
    (net (code "147") (name "unconnected-(IC33O-IO_L7N_36-PadM17)") (class "Default")
      (node (ref "IC33") (pin "M17") (pinfunction "IO_L7N_36_M17") (pintype "bidirectional"))
    )
    (net (code "148") (name "unconnected-(IC33O-IO_L7P_36-PadM18)") (class "Default")
      (node (ref "IC33") (pin "M18") (pinfunction "IO_L7P_36_M18") (pintype "bidirectional"))
    )
    (net (code "149") (name "unconnected-(IC33O-IO_L8N_SRCC_36-PadH18)") (class "Default")
      (node (ref "IC33") (pin "H18") (pinfunction "IO_L8N_SRCC_36_H18") (pintype "bidirectional"))
    )
    (net (code "150") (name "unconnected-(IC33O-IO_L8P_SRCC_36-PadG18)") (class "Default")
      (node (ref "IC33") (pin "G18") (pinfunction "IO_L8P_SRCC_36_G18") (pintype "bidirectional"))
    )
    (net (code "151") (name "unconnected-(IC33O-IO_L9N_MRCC_36-PadL16)") (class "Default")
      (node (ref "IC33") (pin "L16") (pinfunction "IO_L9N_MRCC_36_L16") (pintype "bidirectional"))
    )
    (net (code "152") (name "unconnected-(IC33O-IO_L9P_MRCC_36-PadK16)") (class "Default")
      (node (ref "IC33") (pin "K16") (pinfunction "IO_L9P_MRCC_36_K16") (pintype "bidirectional"))
    )
    (net (code "153") (name "unconnected-(IC33O-IO_L10N_MRCC_36-PadL14)") (class "Default")
      (node (ref "IC33") (pin "L14") (pinfunction "IO_L10N_MRCC_36_L14") (pintype "bidirectional"))
    )
    (net (code "154") (name "unconnected-(IC33O-IO_L10P_MRCC_36-PadL15)") (class "Default")
      (node (ref "IC33") (pin "L15") (pinfunction "IO_L10P_MRCC_36_L15") (pintype "bidirectional"))
    )
    (net (code "155") (name "unconnected-(IC33O-IO_L11N_SRCC_36-PadB16)") (class "Default")
      (node (ref "IC33") (pin "B16") (pinfunction "IO_L11N_SRCC_36_B16") (pintype "bidirectional"))
    )
    (net (code "156") (name "unconnected-(IC33O-IO_L11P_SRCC_36-PadA16)") (class "Default")
      (node (ref "IC33") (pin "A16") (pinfunction "IO_L11P_SRCC_36_A16") (pintype "bidirectional"))
    )
    (net (code "157") (name "unconnected-(IC33O-IO_L12N_VRP_36-PadG16)") (class "Default")
      (node (ref "IC33") (pin "G16") (pinfunction "IO_L12N_VRP_36_G16") (pintype "bidirectional"))
    )
    (net (code "158") (name "unconnected-(IC33O-IO_L12P_VRN_36-PadF16)") (class "Default")
      (node (ref "IC33") (pin "F16") (pinfunction "IO_L12P_VRN_36_F16") (pintype "bidirectional"))
    )
    (net (code "159") (name "unconnected-(IC33O-IO_L13N_36-PadD16)") (class "Default")
      (node (ref "IC33") (pin "D16") (pinfunction "IO_L13N_36_D16") (pintype "bidirectional"))
    )
    (net (code "160") (name "unconnected-(IC33O-IO_L13P_36-PadE16)") (class "Default")
      (node (ref "IC33") (pin "E16") (pinfunction "IO_L13P_36_E16") (pintype "bidirectional"))
    )
    (net (code "161") (name "unconnected-(IC33O-IO_L14N_VREF_36-PadJ16)") (class "Default")
      (node (ref "IC33") (pin "J16") (pinfunction "IO_L14N_VREF_36_J16") (pintype "bidirectional"))
    )
    (net (code "162") (name "unconnected-(IC33O-IO_L14P_36-PadJ17)") (class "Default")
      (node (ref "IC33") (pin "J17") (pinfunction "IO_L14P_36_J17") (pintype "bidirectional"))
    )
    (net (code "163") (name "unconnected-(IC33O-IO_L15N_36-PadB15)") (class "Default")
      (node (ref "IC33") (pin "B15") (pinfunction "IO_L15N_36_B15") (pintype "bidirectional"))
    )
    (net (code "164") (name "unconnected-(IC33O-IO_L15P_36-PadA15)") (class "Default")
      (node (ref "IC33") (pin "A15") (pinfunction "IO_L15P_36_A15") (pintype "bidirectional"))
    )
    (net (code "165") (name "unconnected-(IC33O-IO_L16N_36-PadF15)") (class "Default")
      (node (ref "IC33") (pin "F15") (pinfunction "IO_L16N_36_F15") (pintype "bidirectional"))
    )
    (net (code "166") (name "unconnected-(IC33O-IO_L16P_36-PadG15)") (class "Default")
      (node (ref "IC33") (pin "G15") (pinfunction "IO_L16P_36_G15") (pintype "bidirectional"))
    )
    (net (code "167") (name "unconnected-(IC33O-IO_L17N_36-PadM15)") (class "Default")
      (node (ref "IC33") (pin "M15") (pinfunction "IO_L17N_36_M15") (pintype "bidirectional"))
    )
    (net (code "168") (name "unconnected-(IC33O-IO_L17P_36-PadM16)") (class "Default")
      (node (ref "IC33") (pin "M16") (pinfunction "IO_L17P_36_M16") (pintype "bidirectional"))
    )
    (net (code "169") (name "unconnected-(IC33O-IO_L18N_36-PadJ15)") (class "Default")
      (node (ref "IC33") (pin "J15") (pinfunction "IO_L18N_36_J15") (pintype "bidirectional"))
    )
    (net (code "170") (name "unconnected-(IC33O-IO_L18P_36-PadH15)") (class "Default")
      (node (ref "IC33") (pin "H15") (pinfunction "IO_L18P_36_H15") (pintype "bidirectional"))
    )
    (net (code "171") (name "unconnected-(IC33O-IO_L19N_36-PadC15)") (class "Default")
      (node (ref "IC33") (pin "C15") (pinfunction "IO_L19N_36_C15") (pintype "bidirectional"))
    )
    (net (code "172") (name "unconnected-(IC33O-IO_L19P_36-PadD15)") (class "Default")
      (node (ref "IC33") (pin "D15") (pinfunction "IO_L19P_36_D15") (pintype "bidirectional"))
    )
  )
)
